# LED.net
KiCad netlist of a schematic drawn in EasyEDA Pro
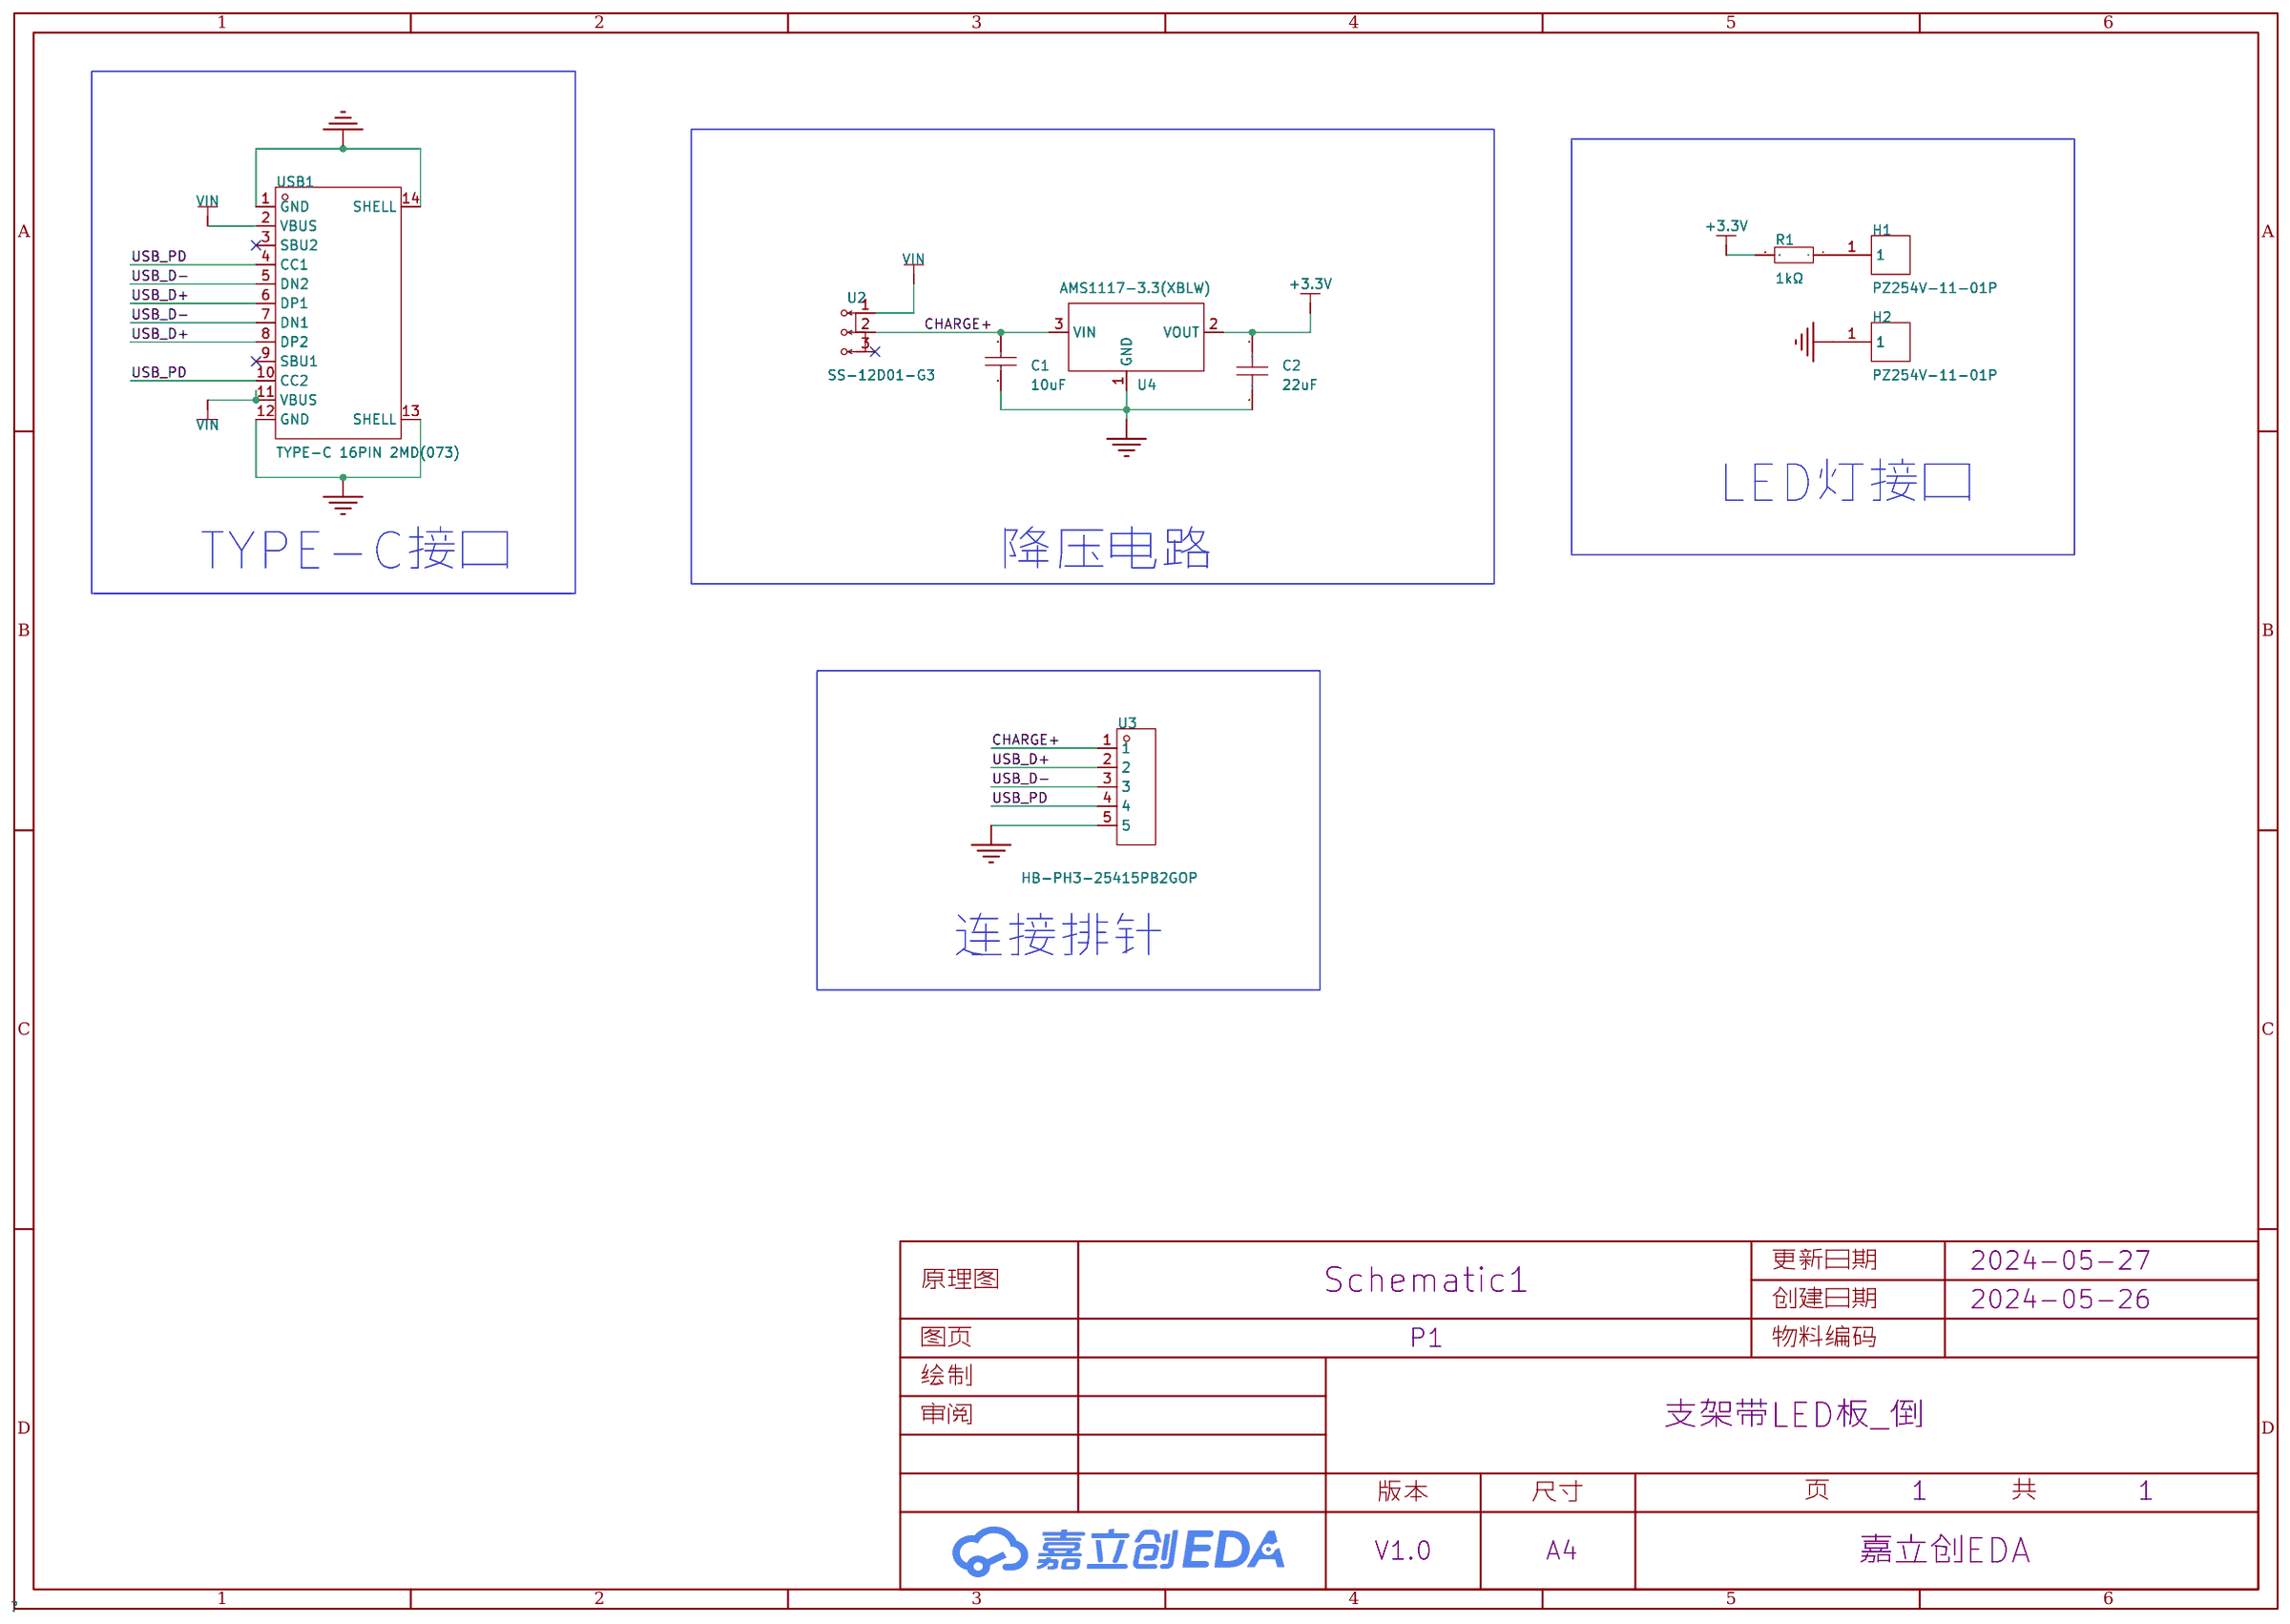
[diagram p0: schematic sheet]

(export (version "E")
  (design (tool "Eeschema 10.0.6"))
  (components
    (comp (ref "C1")
      (value "10uF")
      (footprint "easyedapro:C1210")
      (description "容值:10uF;精度:±10%;额定电压:50V;材质(温度系数):X7R;")
      (fields (field (name "Manufacturer Part") "1210B106K500NT") (field (name "Manufacturer") "FH(风华)"))
      (libsource (lib "easyedapro") (part "1210B106K500NT"))
    )
    (comp (ref "C2")
      (value "22uF")
      (footprint "easyedapro:C0603")
      (description "容值:22uF;精度:±20%;额定电压:6.3V;材质(温度系数):X5R;")
      (fields
        (field (name "Manufacturer Part") "CL10A226MQ8NRNC")
        (field (name "Manufacturer") "SAMSUNG(三星)")
      )
      (libsource (lib "easyedapro") (part "CL10A226MQ8NRNC"))
    )
    (comp (ref "H1")
      (value "PZ254V-11-01P")
      (footprint "easyedapro:HDR-TH_1P-P2.54-V-M")
      (fields (field (name "Manufacturer") "XFCN(兴飞)"))
      (libsource (lib "easyedapro") (part "PZ254V-11-01P"))
    )
    (comp (ref "H2")
      (value "PZ254V-11-01P")
      (footprint "easyedapro:HDR-TH_1P-P2.54-V-M")
      (fields (field (name "Manufacturer") "XFCN(兴飞)"))
      (libsource (lib "easyedapro") (part "PZ254V-11-01P"))
    )
    (comp (ref "R1")
      (value "1kΩ")
      (footprint "easyedapro:R0805")
      (description "电阻类型:厚膜电阻;阻值:1kΩ;精度:±1%;功率:125mW;最大工作电压:150V;温度系数:±100ppm/°C;")
      (fields (field (name "Manufacturer Part") "RC0805FR-071KL") (field (name "Manufacturer") "YAGEO(国巨)"))
      (libsource (lib "easyedapro") (part "RC0805FR-071KL"))
    )
    (comp (ref "U2")
      (value "SS-12D01-G3")
      (footprint "easyedapro:SW-TH_DEALON_SS-12D01-GX")
      (description "电路结构:单刀双掷;安装方式:直插;开关颜色:黑色;机械寿命:-;")
      (fields (field (name "Manufacturer") "DEALON(德艺隆)"))
      (libsource (lib "easyedapro") (part "SS-12D01-G3_C2998803"))
    )
    (comp (ref "U3")
      (value "HB-PH3-25415PB2GOP")
      (footprint "easyedapro:HDR-TH_5P-P2.54-V-M")
      (fields (field (name "Manufacturer") "HANBO(汉博)"))
      (libsource (lib "easyedapro") (part "HB-PH3-25415PB2GOP"))
    )
    (comp (ref "U4")
      (value "AMS1117-3.3(XBLW)")
      (footprint "easyedapro:SOT-89-3_L4.5-W2.5-P1.50-LS4.2-BR")
      (description "最大输入电压:15V;最大输出电流:1A;")
      (fields (field (name "Manufacturer") "XBLW(芯伯乐)"))
      (libsource (lib "easyedapro") (part "AMS1117-3.3(XBLW)"))
    )
    (comp (ref "USB1")
      (value "TYPE-C 16PIN 2MD(073)")
      (footprint "easyedapro:USB-C-SMD_TYPE-C-6PIN-2MD-073")
      (description "连接器类型:Type-C;标准:-;公母:母;端口数量:1;触点数量:16P;安装方式:卧贴;额定电流 - 电源:5A;工作温度范围:-25°C~+85°C;")
      (fields (field (name "Manufacturer") "SHOU HAN(首韩)"))
      (libsource (lib "easyedapro") (part "TYPE-C 16PIN 2MD(073)"))
    )
  )
  (nets
    (net (code "1") (name "+3.3V") (class "Default")
      (node (ref "C2") (pin "2") (pinfunction "2_2") (pintype "unspecified"))
      (node (ref "R1") (pin "2") (pinfunction "2_2") (pintype "input"))
      (node (ref "U4") (pin "2") (pinfunction "VOUT_2") (pintype "unspecified"))
    )
    (net (code "2") (name "/CHARGE+") (class "Default")
      (node (ref "C1") (pin "2") (pinfunction "2_2") (pintype "input"))
      (node (ref "U2") (pin "2") (pinfunction "2_2") (pintype "unspecified"))
      (node (ref "U3") (pin "1") (pinfunction "1_1") (pintype "unspecified"))
      (node (ref "U4") (pin "3") (pinfunction "VIN_3") (pintype "unspecified"))
    )
    (net (code "3") (name "/USB_D+") (class "Default")
      (node (ref "U3") (pin "2") (pinfunction "2_2") (pintype "unspecified"))
      (node (ref "USB1") (pin "6") (pinfunction "DP1_6") (pintype "unspecified"))
      (node (ref "USB1") (pin "8") (pinfunction "DP2_8") (pintype "unspecified"))
    )
    (net (code "4") (name "/USB_D-") (class "Default")
      (node (ref "U3") (pin "3") (pinfunction "3_3") (pintype "unspecified"))
      (node (ref "USB1") (pin "5") (pinfunction "DN2_5") (pintype "unspecified"))
      (node (ref "USB1") (pin "7") (pinfunction "DN1_7") (pintype "unspecified"))
    )
    (net (code "5") (name "/USB_PD") (class "Default")
      (node (ref "U3") (pin "4") (pinfunction "4_4") (pintype "unspecified"))
      (node (ref "USB1") (pin "10") (pinfunction "CC2_10") (pintype "unspecified"))
      (node (ref "USB1") (pin "4") (pinfunction "CC1_4") (pintype "unspecified"))
    )
    (net (code "6") (name "GND") (class "Default")
      (node (ref "C1") (pin "1") (pinfunction "1_1") (pintype "input"))
      (node (ref "C2") (pin "1") (pinfunction "1_1") (pintype "unspecified"))
      (node (ref "H2") (pin "1") (pinfunction "1_1") (pintype "unspecified"))
      (node (ref "U3") (pin "5") (pinfunction "5_5") (pintype "unspecified"))
      (node (ref "U4") (pin "1") (pinfunction "GND_1") (pintype "unspecified"))
      (node (ref "USB1") (pin "1") (pinfunction "GND_1") (pintype "unspecified"))
      (node (ref "USB1") (pin "12") (pinfunction "GND_12") (pintype "unspecified"))
      (node (ref "USB1") (pin "13") (pinfunction "SHELL_13") (pintype "unspecified"))
      (node (ref "USB1") (pin "14") (pinfunction "SHELL_14") (pintype "unspecified"))
    )
    (net (code "7") (name "Net-(H1-Pad1)") (class "Default")
      (node (ref "H1") (pin "1") (pinfunction "1_1") (pintype "unspecified"))
      (node (ref "R1") (pin "1") (pinfunction "1_1") (pintype "input"))
    )
    (net (code "8") (name "VIN") (class "Default")
      (node (ref "U2") (pin "1") (pinfunction "1_1") (pintype "unspecified"))
      (node (ref "USB1") (pin "11") (pinfunction "VBUS_11") (pintype "unspecified"))
      (node (ref "USB1") (pin "2") (pinfunction "VBUS_2") (pintype "unspecified"))
    )
    (net (code "9") (name "unconnected-(U2-Pad3)") (class "Default")
      (node (ref "U2") (pin "3") (pinfunction "3_3") (pintype "unspecified+no_connect"))
    )
    (net (code "10") (name "unconnected-(USB1-SBU1-Pad9)") (class "Default")
      (node (ref "USB1") (pin "9") (pinfunction "SBU1_9") (pintype "unspecified+no_connect"))
    )
    (net (code "11") (name "unconnected-(USB1-SBU2-Pad3)") (class "Default")
      (node (ref "USB1") (pin "3") (pinfunction "SBU2_3") (pintype "unspecified+no_connect"))
    )
  )
)
